# Adafruit_PyPortal.net
KiCad netlist of a schematic drawn in EAGLE
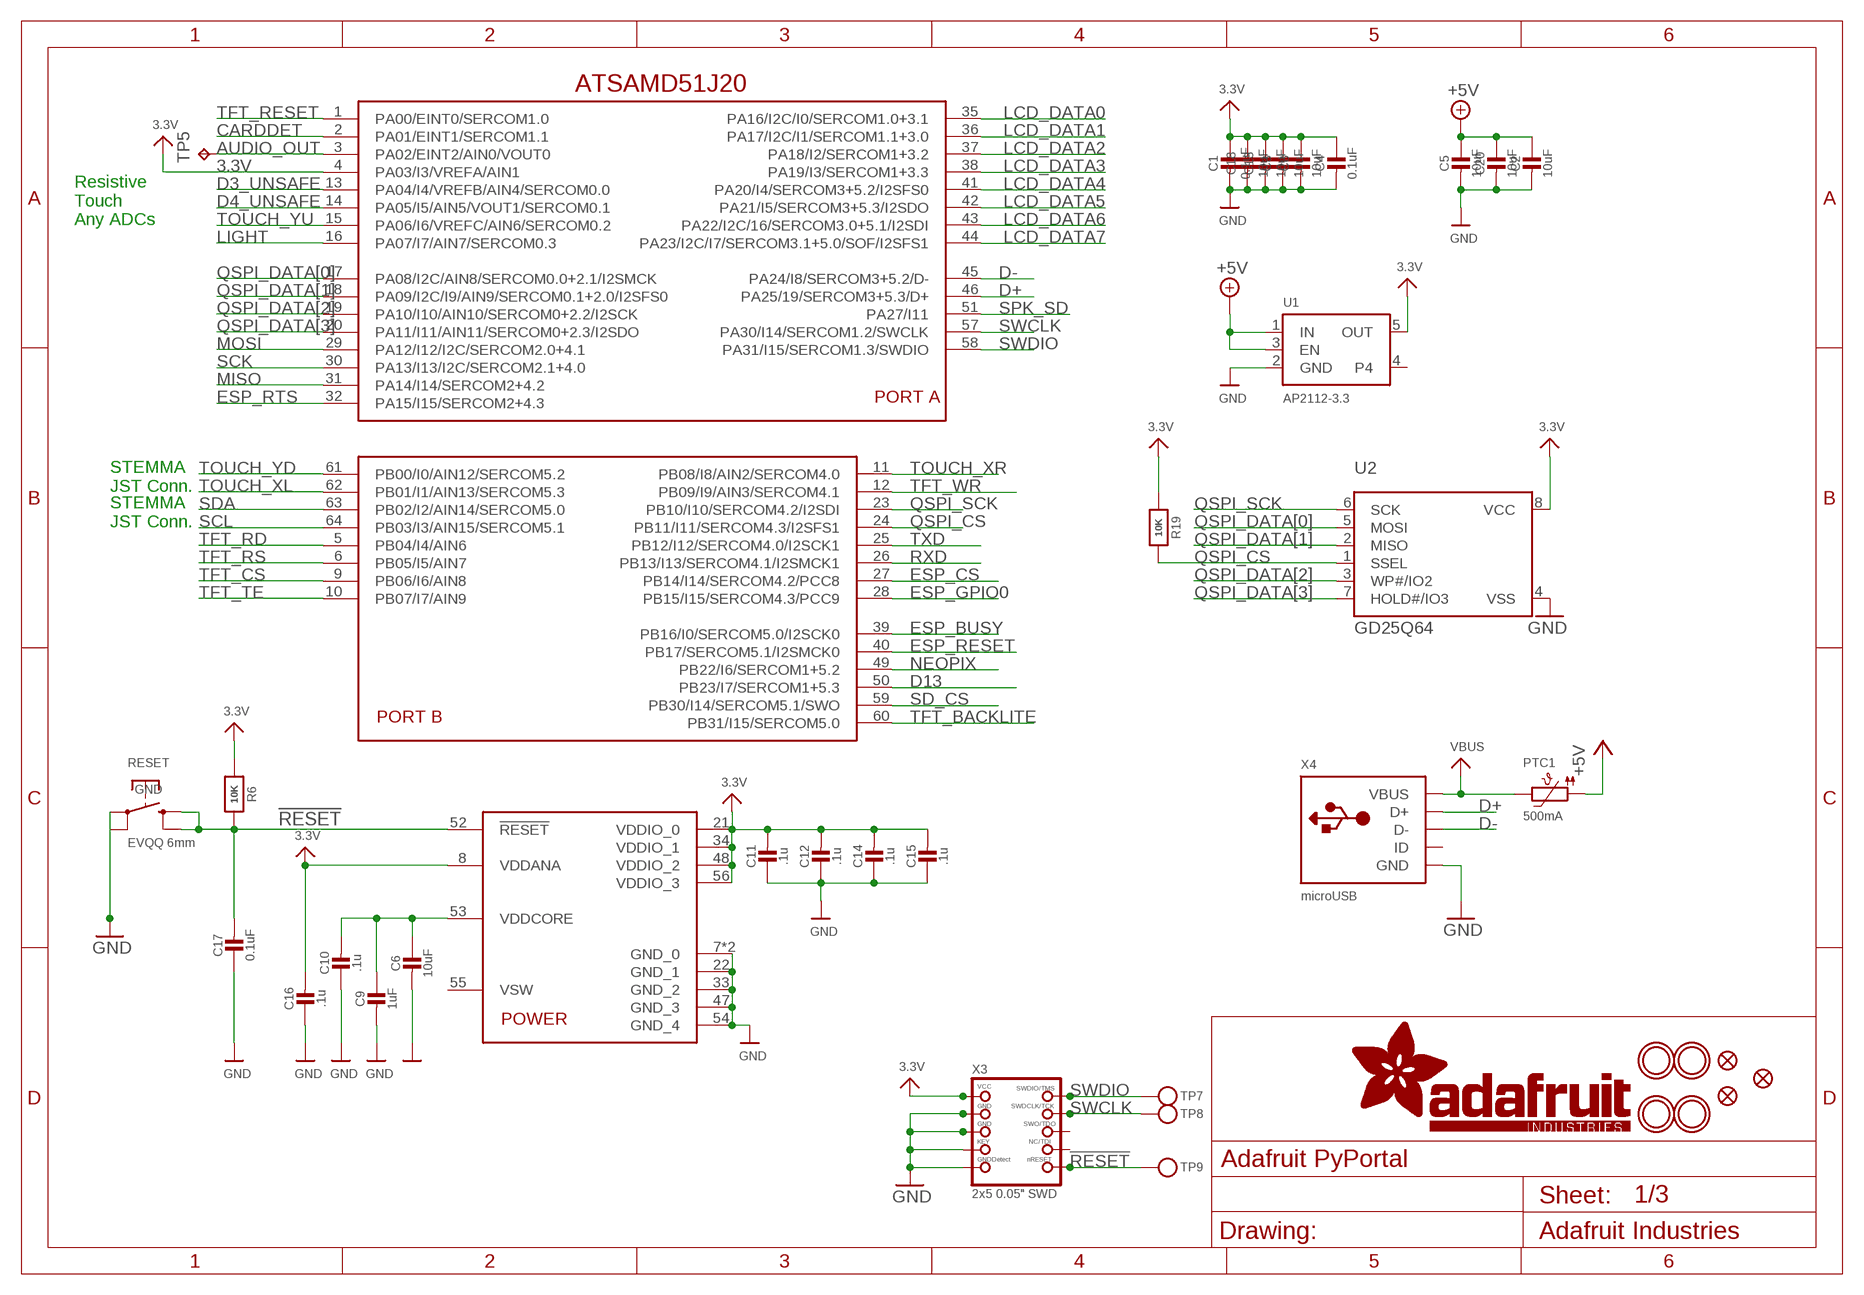
[diagram p0: schematic, sheet 1]
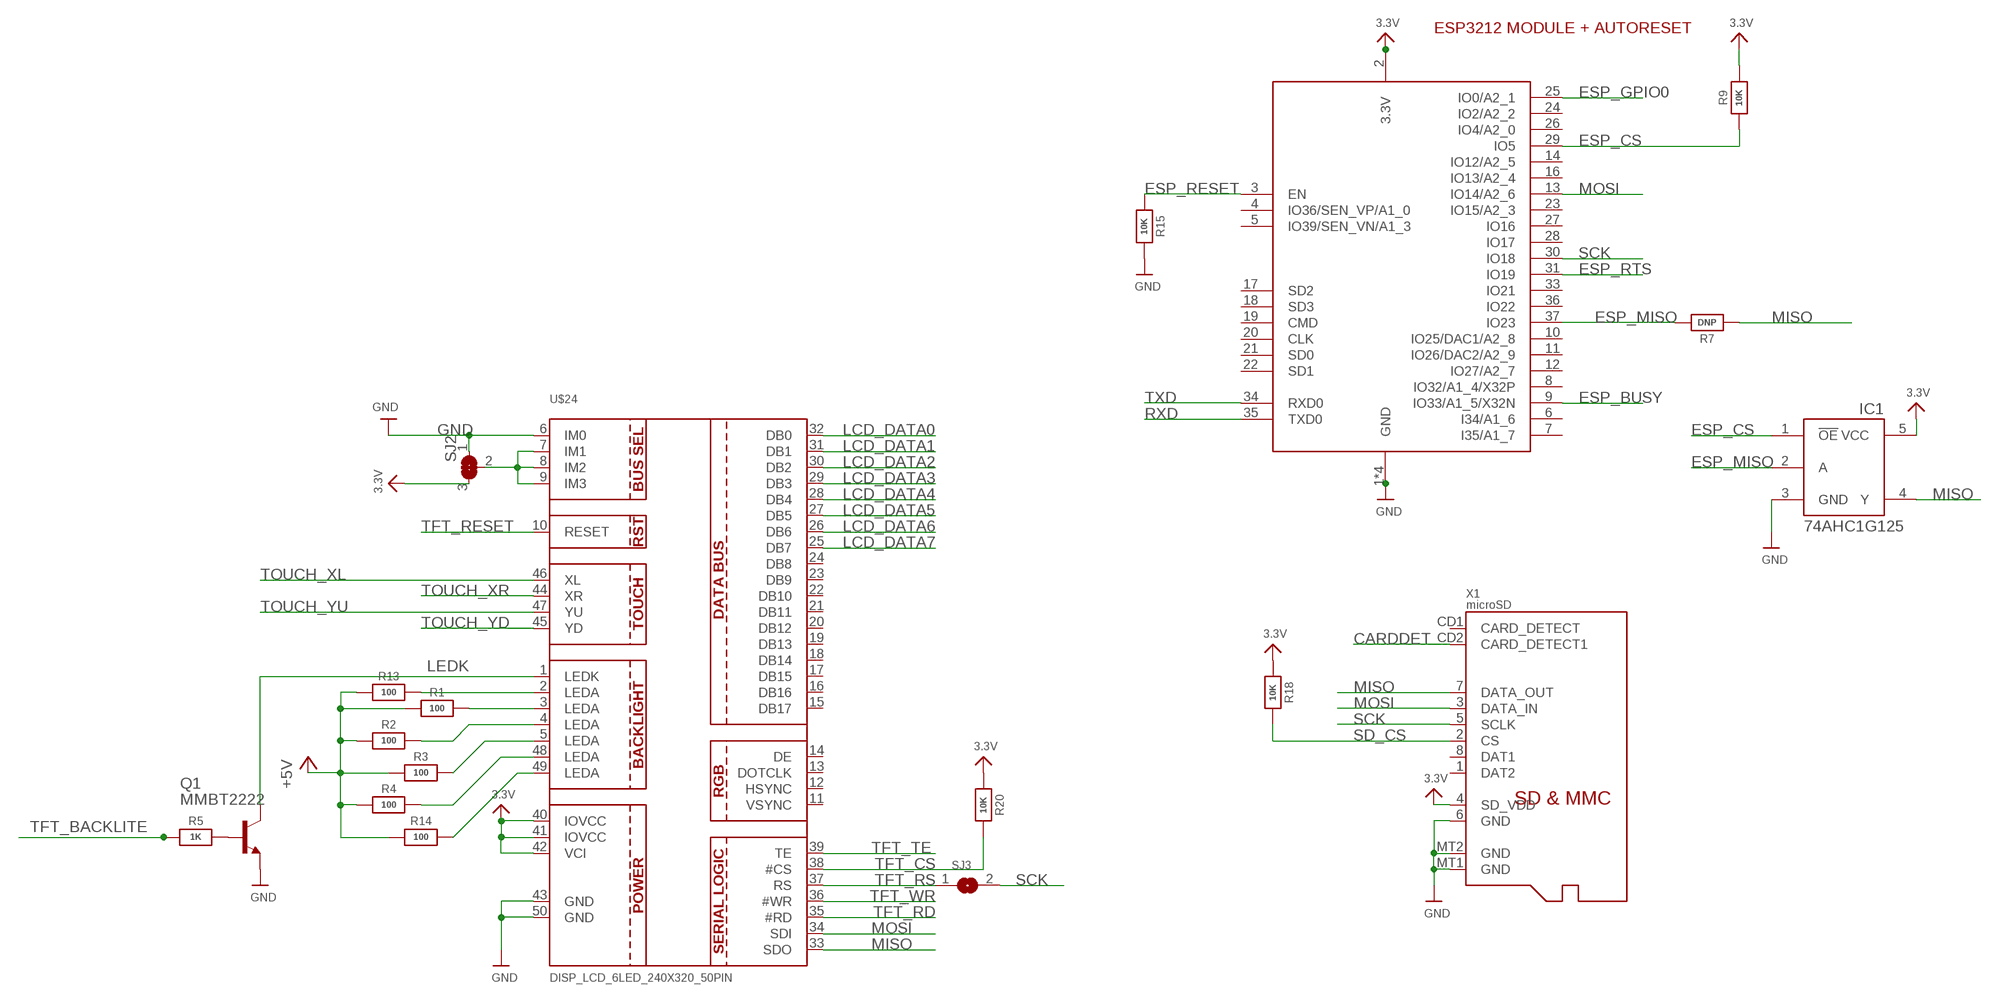
[diagram p1: schematic, sheet 2]
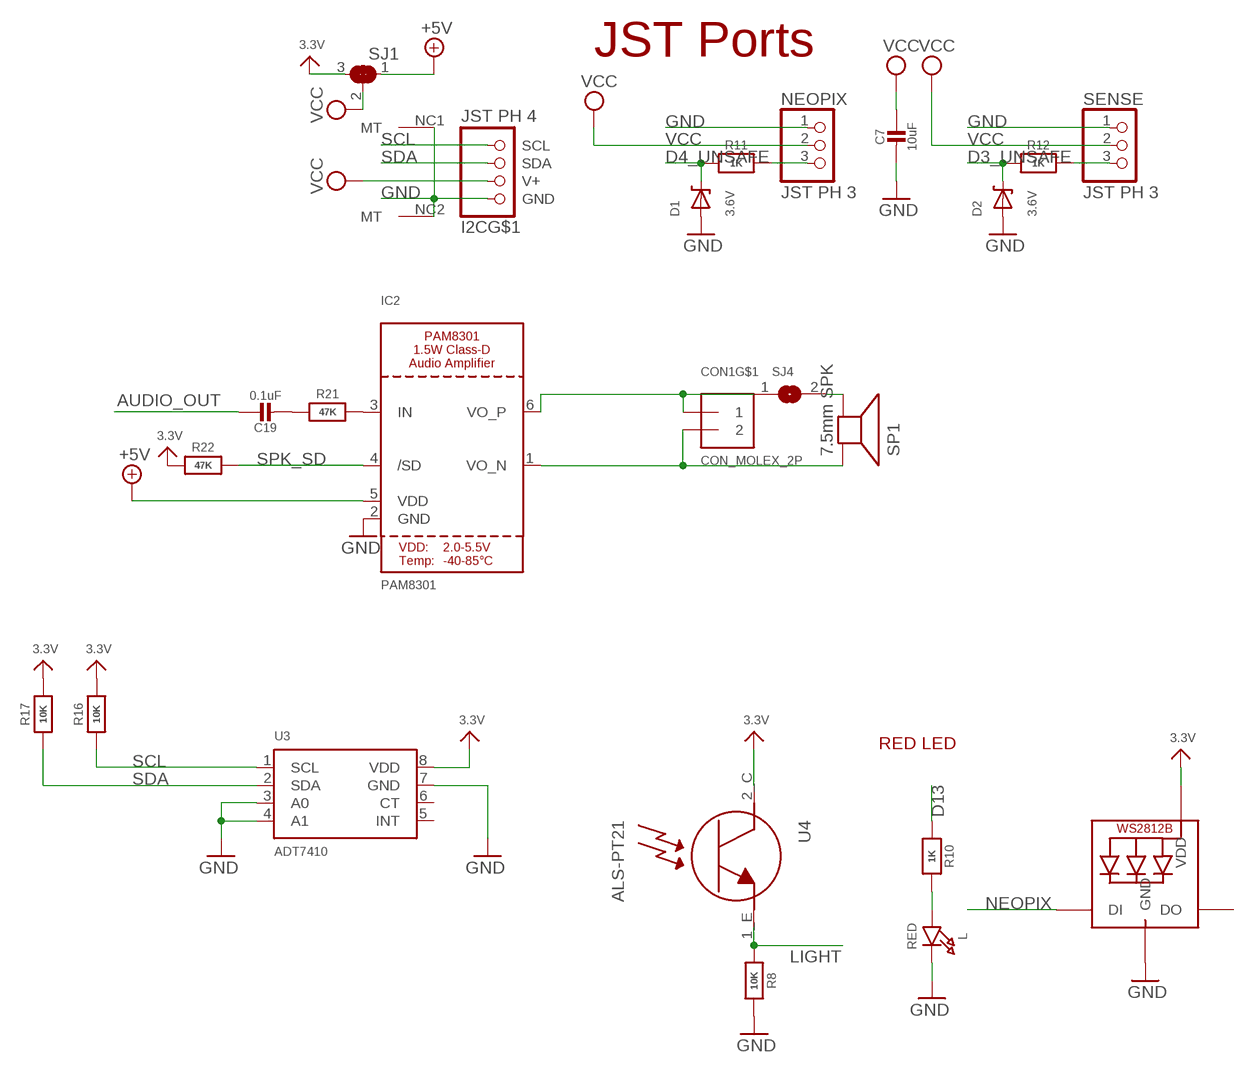
[diagram p2: schematic, sheet 3]

(export (version "E")
  (design (tool "Eeschema 10.0.6"))
  (components
    (comp (ref "IC1")
      (value "74AHC1G125")
      (footprint "eagle-import:SOT23-5L")
      (libsource (lib "eagle-import") (part "74AHC1G125"))
    )
    (comp (ref "Q1")
      (value "MMBT2222")
      (footprint "eagle-import:SOT23-BEC")
      (libsource (lib "eagle-import") (part "-NPN-SOT23-BECMMBT2222ALT1"))
    )
    (comp (ref "R1")
      (value "100")
      (footprint "eagle-import:0603-NO")
      (libsource (lib "eagle-import") (part "RESISTOR_0603_NOOUT"))
    )
    (comp (ref "R2")
      (value "100")
      (footprint "eagle-import:0603-NO")
      (libsource (lib "eagle-import") (part "RESISTOR_0603_NOOUT"))
    )
    (comp (ref "R3")
      (value "100")
      (footprint "eagle-import:0603-NO")
      (libsource (lib "eagle-import") (part "RESISTOR_0603_NOOUT"))
    )
    (comp (ref "R4")
      (value "100")
      (footprint "eagle-import:0603-NO")
      (libsource (lib "eagle-import") (part "RESISTOR_0603_NOOUT"))
    )
    (comp (ref "R5")
      (value "1K")
      (footprint "eagle-import:0603-NO")
      (libsource (lib "eagle-import") (part "RESISTOR_0603_NOOUT"))
    )
    (comp (ref "R7")
      (value "DNP")
      (footprint "eagle-import:0603-NO")
      (libsource (lib "eagle-import") (part "RESISTOR_0603_NOOUT"))
    )
    (comp (ref "R9")
      (value "10K")
      (footprint "eagle-import:0603-NO")
      (libsource (lib "eagle-import") (part "RESISTOR_0603_NOOUT"))
    )
    (comp (ref "R13")
      (value "100")
      (footprint "eagle-import:0603-NO")
      (libsource (lib "eagle-import") (part "RESISTOR_0603_NOOUT"))
    )
    (comp (ref "R14")
      (value "100")
      (footprint "eagle-import:0603-NO")
      (libsource (lib "eagle-import") (part "RESISTOR_0603_NOOUT"))
    )
    (comp (ref "R15")
      (value "10K")
      (footprint "eagle-import:0603-NO")
      (libsource (lib "eagle-import") (part "RESISTOR_0603_NOOUT"))
    )
    (comp (ref "R18")
      (value "10K")
      (footprint "eagle-import:0603-NO")
      (libsource (lib "eagle-import") (part "RESISTOR_0603_NOOUT"))
    )
    (comp (ref "R20")
      (value "10K")
      (footprint "eagle-import:0603-NO")
      (libsource (lib "eagle-import") (part "RESISTOR_0603_NOOUT"))
    )
    (comp (ref "SJ2")
      (value "SOLDERJUMPER_2WAY")
      (footprint "eagle-import:SOLDERJUMPER_2WAY_OPEN_NOPASTE")
      (libsource (lib "eagle-import") (part "SOLDERJUMPER_2WAY"))
    )
    (comp (ref "SJ3")
      (value "SOLDERJUMPER")
      (footprint "eagle-import:SOLDERJUMPER_ARROW_NOPASTE")
      (libsource (lib "eagle-import") (part "SOLDERJUMPER"))
    )
    (comp (ref "U$24")
      (value "DISP_LCD_6LED_240X320_50PIN")
      (footprint "eagle-import:TFT_3.2IN_240X320_50PIN")
      (libsource (lib "eagle-import") (part "DISP_LCD_6LED_240X320_50PIN"))
    )
    (comp (ref "X1")
      (value "microSD")
      (footprint "eagle-import:MICROSD")
      (libsource (lib "eagle-import") (part "MICROSD"))
    )
    (comp (ref "X6")
      (value "ESP32_WROOM32")
      (footprint "eagle-import:WROOM32")
      (libsource (lib "eagle-import") (part "ESP32_WROOM32"))
    )
    (comp (ref "C1")
      (value "0.1uF")
      (footprint "eagle-import:0603-NO")
      (libsource (lib "eagle-import") (part "CAP_CERAMIC0603_NO"))
    )
    (comp (ref "C2")
      (value "10uF")
      (footprint "eagle-import:0805-NO")
      (libsource (lib "eagle-import") (part "CAP_CERAMIC0805-NOOUTLINE"))
    )
    (comp (ref "C3")
      (value "10uF")
      (footprint "eagle-import:0805-NO")
      (libsource (lib "eagle-import") (part "CAP_CERAMIC0805-NOOUTLINE"))
    )
    (comp (ref "C4")
      (value "0.1uF")
      (footprint "eagle-import:0805-NO")
      (libsource (lib "eagle-import") (part "CAP_CERAMIC0805-NOOUTLINE"))
    )
    (comp (ref "C5")
      (value "10uF")
      (footprint "eagle-import:0805-NO")
      (libsource (lib "eagle-import") (part "CAP_CERAMIC0805-NOOUTLINE"))
    )
    (comp (ref "C6")
      (value "10uF")
      (footprint "eagle-import:0805-NO")
      (libsource (lib "eagle-import") (part "CAP_CERAMIC0805-NOOUTLINE"))
    )
    (comp (ref "C8")
      (value "10uF")
      (footprint "eagle-import:0805-NO")
      (libsource (lib "eagle-import") (part "CAP_CERAMIC0805-NOOUTLINE"))
    )
    (comp (ref "C9")
      (value "1uF")
      (footprint "eagle-import:0603-NO")
      (libsource (lib "eagle-import") (part "CAP_CERAMIC0603_NO"))
    )
    (comp (ref "C10")
      (value ".1u")
      (footprint "eagle-import:0603-NO")
      (libsource (lib "eagle-import") (part "CAP_CERAMIC0603_NO"))
    )
    (comp (ref "C11")
      (value ".1u")
      (footprint "eagle-import:0603-NO")
      (libsource (lib "eagle-import") (part "CAP_CERAMIC0603_NO"))
    )
    (comp (ref "C12")
      (value ".1u")
      (footprint "eagle-import:0603-NO")
      (libsource (lib "eagle-import") (part "CAP_CERAMIC0603_NO"))
    )
    (comp (ref "C13")
      (value "10uF")
      (footprint "eagle-import:0805-NO")
      (libsource (lib "eagle-import") (part "CAP_CERAMIC0805-NOOUTLINE"))
    )
    (comp (ref "C14")
      (value ".1u")
      (footprint "eagle-import:0603-NO")
      (libsource (lib "eagle-import") (part "CAP_CERAMIC0603_NO"))
    )
    (comp (ref "C15")
      (value ".1u")
      (footprint "eagle-import:0603-NO")
      (libsource (lib "eagle-import") (part "CAP_CERAMIC0603_NO"))
    )
    (comp (ref "C16")
      (value ".1u")
      (footprint "eagle-import:0603-NO")
      (libsource (lib "eagle-import") (part "CAP_CERAMIC0603_NO"))
    )
    (comp (ref "C17")
      (value "0.1uF")
      (footprint "eagle-import:0603-NO")
      (libsource (lib "eagle-import") (part "CAP_CERAMIC0603_NO"))
    )
    (comp (ref "C18")
      (value "10uF")
      (footprint "eagle-import:0805-NO")
      (libsource (lib "eagle-import") (part "CAP_CERAMIC0805-NOOUTLINE"))
    )
    (comp (ref "C20")
      (value "10uF")
      (footprint "eagle-import:0805-NO")
      (libsource (lib "eagle-import") (part "CAP_CERAMIC0805-NOOUTLINE"))
    )
    (comp (ref "PTC1")
      (value "500mA")
      (footprint "eagle-import:1206")
      (libsource (lib "eagle-import") (part "PTC1206"))
    )
    (comp (ref "R6")
      (value "10K")
      (footprint "eagle-import:0603-NO")
      (libsource (lib "eagle-import") (part "RESISTOR_0603_NOOUT"))
    )
    (comp (ref "R19")
      (value "10K")
      (footprint "eagle-import:0603-NO")
      (libsource (lib "eagle-import") (part "RESISTOR_0603_NOOUT"))
    )
    (comp (ref "RESET")
      (value "EVQQ 6mm")
      (footprint "eagle-import:EVQ-Q2_SMALLER")
      (libsource (lib "eagle-import") (part "SWITCH_TACT_SMT_EVQQ2_SMALL"))
    )
    (comp (ref "TP5")
      (value "TPTP15R")
      (footprint "eagle-import:TP15R")
      (libsource (lib "eagle-import") (part "TPTP15R"))
    )
    (comp (ref "TP7")
      (value "TESTPOINTROUND1.5MM")
      (footprint "eagle-import:TESTPOINT_ROUND_1.5MM")
      (libsource (lib "eagle-import") (part "TESTPOINTROUND1.5MM"))
    )
    (comp (ref "TP8")
      (value "TESTPOINTROUND1.5MM")
      (footprint "eagle-import:TESTPOINT_ROUND_1.5MM")
      (libsource (lib "eagle-import") (part "TESTPOINTROUND1.5MM"))
    )
    (comp (ref "TP9")
      (value "TESTPOINTROUND1.5MM")
      (footprint "eagle-import:TESTPOINT_ROUND_1.5MM")
      (libsource (lib "eagle-import") (part "TESTPOINTROUND1.5MM"))
    )
    (comp (ref "U$2")
      (value "ATSAMD51J20")
      (footprint "eagle-import:PQFN64-1")
      (libsource (lib "eagle-import") (part "ATSAMD51J"))
    )
    (comp (ref "U$7")
      (value "MOUNTINGHOLE3.0THIN")
      (footprint "eagle-import:MOUNTINGHOLE_3.0_PLATEDTHIN")
      (libsource (lib "eagle-import") (part "MOUNTINGHOLE3.0THIN"))
    )
    (comp (ref "U$9")
      (value "FIDUCIAL_1MM")
      (footprint "eagle-import:FIDUCIAL_1MM")
      (libsource (lib "eagle-import") (part "FIDUCIAL_1MM"))
    )
    (comp (ref "U$11")
      (value "FIDUCIAL_1MM")
      (footprint "eagle-import:FIDUCIAL_1MM")
      (libsource (lib "eagle-import") (part "FIDUCIAL_1MM"))
    )
    (comp (ref "U$15")
      (value "MOUNTINGHOLE3.0THIN")
      (footprint "eagle-import:MOUNTINGHOLE_3.0_PLATEDTHIN")
      (libsource (lib "eagle-import") (part "MOUNTINGHOLE3.0THIN"))
    )
    (comp (ref "U$16")
      (value "MOUNTINGHOLE3.0THIN")
      (footprint "eagle-import:MOUNTINGHOLE_3.0_PLATEDTHIN")
      (libsource (lib "eagle-import") (part "MOUNTINGHOLE3.0THIN"))
    )
    (comp (ref "U$17")
      (value "MOUNTINGHOLE3.0THIN")
      (footprint "eagle-import:MOUNTINGHOLE_3.0_PLATEDTHIN")
      (libsource (lib "eagle-import") (part "MOUNTINGHOLE3.0THIN"))
    )
    (comp (ref "U$23")
      (value "FIDUCIAL_1MM")
      (footprint "eagle-import:FIDUCIAL_1MM")
      (libsource (lib "eagle-import") (part "FIDUCIAL_1MM"))
    )
    (comp (ref "U1")
      (value "AP2112-3.3")
      (footprint "eagle-import:SOT23-5")
      (libsource (lib "eagle-import") (part "VREG_SOT23-5"))
    )
    (comp (ref "U2")
      (value "GD25Q64")
      (footprint "eagle-import:SOIC8_208MIL")
      (libsource (lib "eagle-import") (part "SPIFLASH_8PIN208MIL"))
    )
    (comp (ref "X3")
      (value "2x5 0.05\" SWD")
      (footprint "eagle-import:2X05_1.27MM_BOX_POSTS")
      (libsource (lib "eagle-import") (part "JTAG-CORTEXBOXPOSTS"))
    )
    (comp (ref "X4")
      (value "microUSB")
      (footprint "eagle-import:4UCONN_20329_V2")
      (libsource (lib "eagle-import") (part "USB_MICRO_20329_V2"))
    )
    (comp (ref "C7")
      (value "10uF")
      (footprint "eagle-import:0805-NO")
      (libsource (lib "eagle-import") (part "CAP_CERAMIC0805-NOOUTLINE"))
    )
    (comp (ref "C19")
      (value "0.1uF")
      (footprint "eagle-import:0603-NO")
      (libsource (lib "eagle-import") (part "CAP_CERAMIC0603_NO"))
    )
    (comp (ref "CON1")
      (value "CON_MOLEX_2P")
      (footprint "eagle-import:53398-0271")
      (libsource (lib "eagle-import") (part "CON_MOLEX_2P"))
    )
    (comp (ref "D1")
      (value "3.6V")
      (footprint "eagle-import:SOD-323")
      (libsource (lib "eagle-import") (part "DIODE-ZENERSOD323"))
    )
    (comp (ref "D2")
      (value "3.6V")
      (footprint "eagle-import:SOD-323")
      (libsource (lib "eagle-import") (part "DIODE-ZENERSOD323"))
    )
    (comp (ref "I2C")
      (value "JST PH 4")
      (footprint "eagle-import:JSTPH4")
      (libsource (lib "eagle-import") (part "STEMMA_I2C_RASMT"))
    )
    (comp (ref "IC2")
      (value "PAM8301")
      (footprint "eagle-import:SOT23-6")
      (libsource (lib "eagle-import") (part "PAM8301"))
    )
    (comp (ref "L")
      (value "RED")
      (footprint "eagle-import:CHIPLED_0805_NOOUTLINE")
      (libsource (lib "eagle-import") (part "LED0805_NOOUTLINE"))
    )
    (comp (ref "LED1")
      (value "WS2812B3535")
      (footprint "eagle-import:LED3535")
      (libsource (lib "eagle-import") (part "WS2812B3535"))
    )
    (comp (ref "NEOPIX")
      (value "JST PH 3")
      (footprint "eagle-import:JSTPH3")
      (libsource (lib "eagle-import") (part "CON_JST_PH_3PIN"))
    )
    (comp (ref "R8")
      (value "10K")
      (footprint "eagle-import:0603-NO")
      (libsource (lib "eagle-import") (part "RESISTOR_0603_NOOUT"))
    )
    (comp (ref "R10")
      (value "1K")
      (footprint "eagle-import:0603-NO")
      (libsource (lib "eagle-import") (part "RESISTOR_0603_NOOUT"))
    )
    (comp (ref "R11")
      (value "1K")
      (footprint "eagle-import:0603-NO")
      (libsource (lib "eagle-import") (part "RESISTOR_0603_NOOUT"))
    )
    (comp (ref "R12")
      (value "1K")
      (footprint "eagle-import:0603-NO")
      (libsource (lib "eagle-import") (part "RESISTOR_0603_NOOUT"))
    )
    (comp (ref "R16")
      (value "10K")
      (footprint "eagle-import:0603-NO")
      (libsource (lib "eagle-import") (part "RESISTOR_0603_NOOUT"))
    )
    (comp (ref "R17")
      (value "10K")
      (footprint "eagle-import:0603-NO")
      (libsource (lib "eagle-import") (part "RESISTOR_0603_NOOUT"))
    )
    (comp (ref "R21")
      (value "47K")
      (footprint "eagle-import:0603-NO")
      (libsource (lib "eagle-import") (part "RESISTOR_0603_NOOUT"))
    )
    (comp (ref "R22")
      (value "47K")
      (footprint "eagle-import:0603-NO")
      (libsource (lib "eagle-import") (part "RESISTOR_0603_NOOUT"))
    )
    (comp (ref "SENSE")
      (value "JST PH 3")
      (footprint "eagle-import:JSTPH3")
      (libsource (lib "eagle-import") (part "CON_JST_PH_3PIN"))
    )
    (comp (ref "SJ1")
      (value "SOLDERJUMPER_2WAY")
      (footprint "eagle-import:SOLDERJUMPER_2WAY_OPEN_NOPASTE")
      (libsource (lib "eagle-import") (part "SOLDERJUMPER_2WAY"))
    )
    (comp (ref "SJ4")
      (value "SOLDERJUMPERCLOSED")
      (footprint "eagle-import:SOLDERJUMPER_CLOSEDWIRE")
      (libsource (lib "eagle-import") (part "SOLDERJUMPERCLOSED"))
    )
    (comp (ref "SP1")
      (value "7.5mm SPK")
      (footprint "eagle-import:BUZZER_SMT_7.5MM")
      (libsource (lib "eagle-import") (part "SPEAKER_7.5MM"))
    )
    (comp (ref "U3")
      (value "ADT7410")
      (footprint "eagle-import:SOIC8_150MIL")
      (libsource (lib "eagle-import") (part "TEMP_ADT7410"))
    )
    (comp (ref "U4")
      (value "ALS-PT21")
      (footprint "eagle-import:ALS-PT26-21C")
      (libsource (lib "eagle-import") (part "PHOTOTRANSISTOR_PT26-21C"))
    )
  )
  (nets
    (net (code "1") (name "+5V") (class "Default")
      (node (ref "C2") (pin "1") (pinfunction "1_1") (pintype "passive"))
      (node (ref "C20") (pin "1") (pinfunction "1_1") (pintype "passive"))
      (node (ref "C5") (pin "1") (pinfunction "1_1") (pintype "passive"))
      (node (ref "IC2") (pin "5") (pinfunction "VDD_5") (pintype "power_in"))
      (node (ref "PTC1") (pin "1") (pinfunction "1_1") (pintype "passive"))
      (node (ref "R1") (pin "1") (pinfunction "1_1") (pintype "passive"))
      (node (ref "R13") (pin "1") (pinfunction "1_1") (pintype "passive"))
      (node (ref "R14") (pin "1") (pinfunction "1_1") (pintype "passive"))
      (node (ref "R2") (pin "1") (pinfunction "1_1") (pintype "passive"))
      (node (ref "R3") (pin "1") (pinfunction "1_1") (pintype "passive"))
      (node (ref "R4") (pin "1") (pinfunction "1_1") (pintype "passive"))
      (node (ref "SJ1") (pin "1") (pinfunction "1_1") (pintype "passive"))
      (node (ref "U1") (pin "1") (pinfunction "IN_1") (pintype "power_in"))
      (node (ref "U1") (pin "3") (pinfunction "EN_3") (pintype "input"))
    )
    (net (code "2") (name "3.3V") (class "Default")
      (node (ref "C1") (pin "1") (pinfunction "1_1") (pintype "passive"))
      (node (ref "C11") (pin "2") (pinfunction "2_2") (pintype "passive"))
      (node (ref "C12") (pin "2") (pinfunction "2_2") (pintype "passive"))
      (node (ref "C13") (pin "1") (pinfunction "1_1") (pintype "passive"))
      (node (ref "C14") (pin "2") (pinfunction "2_2") (pintype "passive"))
      (node (ref "C15") (pin "2") (pinfunction "2_2") (pintype "passive"))
      (node (ref "C16") (pin "2") (pinfunction "2_2") (pintype "passive"))
      (node (ref "C18") (pin "1") (pinfunction "1_1") (pintype "passive"))
      (node (ref "C3") (pin "1") (pinfunction "1_1") (pintype "passive"))
      (node (ref "C4") (pin "1") (pinfunction "1_1") (pintype "passive"))
      (node (ref "C8") (pin "1") (pinfunction "1_1") (pintype "passive"))
      (node (ref "IC1") (pin "5") (pinfunction "VCC_5") (pintype "power_in"))
      (node (ref "LED1") (pin "2") (pinfunction "VDD_2") (pintype "power_in"))
      (node (ref "R16") (pin "1") (pinfunction "1_1") (pintype "passive"))
      (node (ref "R17") (pin "1") (pinfunction "1_1") (pintype "passive"))
      (node (ref "R18") (pin "1") (pinfunction "1_1") (pintype "passive"))
      (node (ref "R19") (pin "1") (pinfunction "1_1") (pintype "passive"))
      (node (ref "R20") (pin "1") (pinfunction "1_1") (pintype "passive"))
      (node (ref "R22") (pin "1") (pinfunction "1_1") (pintype "passive"))
      (node (ref "R6") (pin "1") (pinfunction "1_1") (pintype "passive"))
      (node (ref "R9") (pin "2") (pinfunction "2_2") (pintype "passive"))
      (node (ref "SJ1") (pin "3") (pinfunction "3_3") (pintype "passive"))
      (node (ref "SJ2") (pin "3") (pinfunction "3_3") (pintype "passive"))
      (node (ref "U$2") (pin "21") (pinfunction "VDDIO_0_21") (pintype "bidirectional"))
      (node (ref "U$2") (pin "34") (pinfunction "VDDIO_1_34") (pintype "bidirectional"))
      (node (ref "U$2") (pin "4") (pinfunction "PA03/I3/VREFA/AIN1_4") (pintype "bidirectional"))
      (node (ref "U$2") (pin "48") (pinfunction "VDDIO_2_48") (pintype "bidirectional"))
      (node (ref "U$2") (pin "56") (pinfunction "VDDIO_3_56") (pintype "bidirectional"))
      (node (ref "U$2") (pin "8") (pinfunction "VDDANA_8") (pintype "bidirectional"))
      (node (ref "U$24") (pin "40") (pinfunction "IOVCC_40") (pintype "bidirectional"))
      (node (ref "U$24") (pin "41") (pinfunction "IOVCC_41") (pintype "bidirectional"))
      (node (ref "U$24") (pin "42") (pinfunction "VCI_42") (pintype "bidirectional"))
      (node (ref "U1") (pin "5") (pinfunction "OUT_5") (pintype "power_in"))
      (node (ref "U2") (pin "8") (pinfunction "VCC_8") (pintype "bidirectional"))
      (node (ref "U3") (pin "8") (pinfunction "VDD_8") (pintype "power_in"))
      (node (ref "U4") (pin "2_C") (pinfunction "C_2_C") (pintype "bidirectional"))
      (node (ref "X1") (pin "4") (pinfunction "SD_VDD_4") (pintype "power_in"))
      (node (ref "X3") (pin "1") (pinfunction "VCC_1") (pintype "power_in"))
      (node (ref "X6") (pin "2") (pinfunction "3.3V_2") (pintype "passive"))
    )
    (net (code "3") (name "AUDIO_OUT") (class "Default")
      (node (ref "C19") (pin "1") (pinfunction "1_1") (pintype "passive"))
      (node (ref "TP5") (pin "TP") (pinfunction "TP_TP") (pintype "input"))
      (node (ref "U$2") (pin "3") (pinfunction "PA02/EINT2/AIN0/VOUT0_3") (pintype "bidirectional"))
    )
    (net (code "4") (name "CARDDET") (class "Default")
      (node (ref "U$2") (pin "2") (pinfunction "PA01/EINT1/SERCOM1.1_2") (pintype "bidirectional"))
      (node (ref "X1") (pin "CD2") (pinfunction "CARD_DETECT1_CD2") (pintype "passive"))
    )
    (net (code "5") (name "D+") (class "Default")
      (node (ref "U$2") (pin "46") (pinfunction "PA25/19/SERCOM3+5.3/D+_46") (pintype "bidirectional"))
      (node (ref "X4") (pin "D+") (pinfunction "D+_D+") (pintype "bidirectional"))
    )
    (net (code "6") (name "D-") (class "Default")
      (node (ref "U$2") (pin "45") (pinfunction "PA24/I8/SERCOM3+5.2/D-_45") (pintype "bidirectional"))
      (node (ref "X4") (pin "D-") (pinfunction "D-_D-") (pintype "bidirectional"))
    )
    (net (code "7") (name "D3_UNSAFE") (class "Default")
      (node (ref "D2") (pin "C") (pinfunction "C_C") (pintype "passive"))
      (node (ref "R12") (pin "2") (pinfunction "2_2") (pintype "passive"))
      (node (ref "U$2") (pin "13") (pinfunction "PA04/I4/VREFB/AIN4/SERCOM0.0_13") (pintype "bidirectional"))
    )
    (net (code "8") (name "D4_UNSAFE") (class "Default")
      (node (ref "D1") (pin "C") (pinfunction "C_C") (pintype "passive"))
      (node (ref "R11") (pin "2") (pinfunction "2_2") (pintype "passive"))
      (node (ref "U$2") (pin "14") (pinfunction "PA05/I5/AIN5/VOUT1/SERCOM0.1_14") (pintype "bidirectional"))
    )
    (net (code "9") (name "D13") (class "Default")
      (node (ref "R10") (pin "1") (pinfunction "1_1") (pintype "passive"))
      (node (ref "U$2") (pin "50") (pinfunction "PB23/I7/SERCOM1+5.3_50") (pintype "bidirectional"))
    )
    (net (code "10") (name "ESP_BUSY") (class "Default")
      (node (ref "U$2") (pin "39") (pinfunction "PB16/I0/SERCOM5.0/I2SCK0_39") (pintype "bidirectional"))
      (node (ref "X6") (pin "9") (pinfunction "IO33/A1_5/X32N_9") (pintype "bidirectional"))
    )
    (net (code "11") (name "ESP_CS") (class "Default")
      (node (ref "IC1") (pin "1") (pinfunction "~{OE}_1") (pintype "input"))
      (node (ref "R9") (pin "1") (pinfunction "1_1") (pintype "passive"))
      (node (ref "U$2") (pin "27") (pinfunction "PB14/I14/SERCOM4.2/PCC8_27") (pintype "bidirectional"))
      (node (ref "X6") (pin "29") (pinfunction "IO5_29") (pintype "bidirectional"))
    )
    (net (code "12") (name "ESP_GPIO0") (class "Default")
      (node (ref "U$2") (pin "28") (pinfunction "PB15/I15/SERCOM4.3/PCC9_28") (pintype "bidirectional"))
      (node (ref "X6") (pin "25") (pinfunction "IO0/A2_1_25") (pintype "bidirectional"))
    )
    (net (code "13") (name "ESP_MISO") (class "Default")
      (node (ref "IC1") (pin "2") (pinfunction "A_2") (pintype "input"))
      (node (ref "R7") (pin "2") (pinfunction "2_2") (pintype "passive"))
      (node (ref "X6") (pin "37") (pinfunction "IO23_37") (pintype "bidirectional"))
    )
    (net (code "14") (name "ESP_RESET") (class "Default")
      (node (ref "R15") (pin "1") (pinfunction "1_1") (pintype "passive"))
      (node (ref "U$2") (pin "40") (pinfunction "PB17/SERCOM5.1/I2SMCK0_40") (pintype "bidirectional"))
      (node (ref "X6") (pin "3") (pinfunction "EN_3") (pintype "input"))
    )
    (net (code "15") (name "ESP_RTS") (class "Default")
      (node (ref "U$2") (pin "32") (pinfunction "PA15/I15/SERCOM2+4.3_32") (pintype "bidirectional"))
      (node (ref "X6") (pin "31") (pinfunction "IO19_31") (pintype "bidirectional"))
    )
    (net (code "16") (name "GND") (class "Default")
      (node (ref "C1") (pin "2") (pinfunction "2_2") (pintype "passive"))
      (node (ref "C10") (pin "1") (pinfunction "1_1") (pintype "passive"))
      (node (ref "C11") (pin "1") (pinfunction "1_1") (pintype "passive"))
      (node (ref "C12") (pin "1") (pinfunction "1_1") (pintype "passive"))
      (node (ref "C13") (pin "2") (pinfunction "2_2") (pintype "passive"))
      (node (ref "C14") (pin "1") (pinfunction "1_1") (pintype "passive"))
      (node (ref "C15") (pin "1") (pinfunction "1_1") (pintype "passive"))
      (node (ref "C16") (pin "1") (pinfunction "1_1") (pintype "passive"))
      (node (ref "C17") (pin "1") (pinfunction "1_1") (pintype "passive"))
      (node (ref "C18") (pin "2") (pinfunction "2_2") (pintype "passive"))
      (node (ref "C2") (pin "2") (pinfunction "2_2") (pintype "passive"))
      (node (ref "C20") (pin "2") (pinfunction "2_2") (pintype "passive"))
      (node (ref "C3") (pin "2") (pinfunction "2_2") (pintype "passive"))
      (node (ref "C4") (pin "2") (pinfunction "2_2") (pintype "passive"))
      (node (ref "C5") (pin "2") (pinfunction "2_2") (pintype "passive"))
      (node (ref "C6") (pin "2") (pinfunction "2_2") (pintype "passive"))
      (node (ref "C7") (pin "2") (pinfunction "2_2") (pintype "passive"))
      (node (ref "C8") (pin "2") (pinfunction "2_2") (pintype "passive"))
      (node (ref "C9") (pin "2") (pinfunction "2_2") (pintype "passive"))
      (node (ref "D1") (pin "A") (pinfunction "A_A") (pintype "passive"))
      (node (ref "D2") (pin "A") (pinfunction "A_A") (pintype "passive"))
      (node (ref "I2C") (pin "1") (pinfunction "GND_1") (pintype "passive"))
      (node (ref "I2C") (pin "NC1") (pinfunction "MT_NC1") (pintype "bidirectional"))
      (node (ref "I2C") (pin "NC2") (pinfunction "MT_NC2") (pintype "bidirectional"))
      (node (ref "IC1") (pin "3") (pinfunction "GND_3") (pintype "power_in"))
      (node (ref "IC2") (pin "2") (pinfunction "GND_2") (pintype "power_in"))
      (node (ref "L") (pin "C") (pinfunction "C_C") (pintype "passive"))
      (node (ref "LED1") (pin "4") (pinfunction "GND_4") (pintype "power_in"))
      (node (ref "NEOPIX") (pin "1") (pinfunction "1_1") (pintype "passive"))
      (node (ref "Q1") (pin "E") (pinfunction "E_E") (pintype "passive"))
      (node (ref "R15") (pin "2") (pinfunction "2_2") (pintype "passive"))
      (node (ref "R8") (pin "1") (pinfunction "1_1") (pintype "passive"))
      (node (ref "RESET") (pin "A") (pinfunction "P_A") (pintype "passive"))
      (node (ref "RESET") (pin "A'") (pinfunction "P1_A'") (pintype "passive"))
      (node (ref "SENSE") (pin "1") (pinfunction "1_1") (pintype "passive"))
      (node (ref "SJ2") (pin "1") (pinfunction "1_1") (pintype "passive"))
      (node (ref "U$2") (pin "22") (pinfunction "GND_1_22") (pintype "bidirectional"))
      (node (ref "U$2") (pin "33") (pinfunction "GND_2_33") (pintype "bidirectional"))
      (node (ref "U$2") (pin "47") (pinfunction "GND_3_47") (pintype "bidirectional"))
      (node (ref "U$2") (pin "54") (pinfunction "GND_4_54") (pintype "bidirectional"))
      (node (ref "U$2") (pin "7") (pinfunction "GND_0_7") (pintype "bidirectional"))
      (node (ref "U$2") (pin "EXP") (pinfunction "GND_0_EXP") (pintype "bidirectional"))
      (node (ref "U$24") (pin "43") (pinfunction "GND_43") (pintype "bidirectional"))
      (node (ref "U$24") (pin "50") (pinfunction "GND_50") (pintype "bidirectional"))
      (node (ref "U$24") (pin "6") (pinfunction "IM0_6") (pintype "bidirectional"))
      (node (ref "U1") (pin "2") (pinfunction "GND_2") (pintype "power_in"))
      (node (ref "U2") (pin "4") (pinfunction "VSS_4") (pintype "bidirectional"))
      (node (ref "U3") (pin "3") (pinfunction "A0_3") (pintype "bidirectional"))
      (node (ref "U3") (pin "4") (pinfunction "A1_4") (pintype "bidirectional"))
      (node (ref "U3") (pin "7") (pinfunction "GND_7") (pintype "power_in"))
      (node (ref "X1") (pin "6") (pinfunction "GND_6") (pintype "power_in"))
      (node (ref "X1") (pin "MT1") (pinfunction "GND_MT1") (pintype "power_in"))
      (node (ref "X1") (pin "MT2") (pinfunction "GND_MT2") (pintype "power_in"))
      (node (ref "X3") (pin "3") (pinfunction "GND_3") (pintype "power_in"))
      (node (ref "X3") (pin "5") (pinfunction "GND_5") (pintype "power_in"))
      (node (ref "X3") (pin "7") (pinfunction "KEY_7") (pintype "bidirectional"))
      (node (ref "X3") (pin "9") (pinfunction "GNDDETECT_9") (pintype "bidirectional"))
      (node (ref "X4") (pin "BASE@1") (pinfunction "GND_BASE@1") (pintype "power_in"))
      (node (ref "X4") (pin "BASE@2") (pinfunction "GND_BASE@2") (pintype "power_in"))
      (node (ref "X4") (pin "GND") (pinfunction "GND_GND") (pintype "power_in"))
      (node (ref "X4") (pin "SPRT@1") (pinfunction "GND_SPRT@1") (pintype "power_in"))
      (node (ref "X4") (pin "SPRT@2") (pinfunction "GND_SPRT@2") (pintype "power_in"))
      (node (ref "X4") (pin "SPRT@3") (pinfunction "GND_SPRT@3") (pintype "power_in"))
      (node (ref "X4") (pin "SPRT@4") (pinfunction "GND_SPRT@4") (pintype "power_in"))
      (node (ref "X6") (pin "1") (pinfunction "GND_1") (pintype "passive"))
      (node (ref "X6") (pin "15") (pinfunction "GND_15") (pintype "passive"))
      (node (ref "X6") (pin "38") (pinfunction "GND_38") (pintype "passive"))
      (node (ref "X6") (pin "P$1") (pinfunction "GND_P$1") (pintype "passive"))
    )
    (net (code "17") (name "LCD_DATA0") (class "Default")
      (node (ref "U$2") (pin "35") (pinfunction "PA16/I2C/I0/SERCOM1.0+3.1_35") (pintype "bidirectional"))
      (node (ref "U$24") (pin "32") (pinfunction "DB0_32") (pintype "bidirectional"))
    )
    (net (code "18") (name "LCD_DATA1") (class "Default")
      (node (ref "U$2") (pin "36") (pinfunction "PA17/I2C/I1/SERCOM1.1+3.0_36") (pintype "bidirectional"))
      (node (ref "U$24") (pin "31") (pinfunction "DB1_31") (pintype "bidirectional"))
    )
    (net (code "19") (name "LCD_DATA2") (class "Default")
      (node (ref "U$2") (pin "37") (pinfunction "PA18/I2/SERCOM1+3.2_37") (pintype "bidirectional"))
      (node (ref "U$24") (pin "30") (pinfunction "DB2_30") (pintype "bidirectional"))
    )
    (net (code "20") (name "LCD_DATA3") (class "Default")
      (node (ref "U$2") (pin "38") (pinfunction "PA19/I3/SERCOM1+3.3_38") (pintype "bidirectional"))
      (node (ref "U$24") (pin "29") (pinfunction "DB3_29") (pintype "bidirectional"))
    )
    (net (code "21") (name "LCD_DATA4") (class "Default")
      (node (ref "U$2") (pin "41") (pinfunction "PA20/I4/SERCOM3+5.2/I2SFS0_41") (pintype "bidirectional"))
      (node (ref "U$24") (pin "28") (pinfunction "DB4_28") (pintype "bidirectional"))
    )
    (net (code "22") (name "LCD_DATA5") (class "Default")
      (node (ref "U$2") (pin "42") (pinfunction "PA21/I5/SERCOM3+5.3/I2SDO_42") (pintype "bidirectional"))
      (node (ref "U$24") (pin "27") (pinfunction "DB5_27") (pintype "bidirectional"))
    )
    (net (code "23") (name "LCD_DATA6") (class "Default")
      (node (ref "U$2") (pin "43") (pinfunction "PA22/I2C/16/SERCOM3.0+5.1/I2SDI_43") (pintype "bidirectional"))
      (node (ref "U$24") (pin "26") (pinfunction "DB6_26") (pintype "bidirectional"))
    )
    (net (code "24") (name "LCD_DATA7") (class "Default")
      (node (ref "U$2") (pin "44") (pinfunction "PA23/I2C/I7/SERCOM3.1+5.0/SOF/I2SFS1_44") (pintype "bidirectional"))
      (node (ref "U$24") (pin "25") (pinfunction "DB7_25") (pintype "bidirectional"))
    )
    (net (code "25") (name "LEDK") (class "Default")
      (node (ref "Q1") (pin "C") (pinfunction "C_C") (pintype "passive"))
      (node (ref "U$24") (pin "1") (pinfunction "LEDK_1") (pintype "bidirectional"))
    )
    (net (code "26") (name "LIGHT") (class "Default")
      (node (ref "R8") (pin "2") (pinfunction "2_2") (pintype "passive"))
      (node (ref "U$2") (pin "16") (pinfunction "PA07/I7/AIN7/SERCOM0.3_16") (pintype "bidirectional"))
      (node (ref "U4") (pin "1_E") (pinfunction "E_1_E") (pintype "bidirectional"))
    )
    (net (code "27") (name "MISO") (class "Default")
      (node (ref "IC1") (pin "4") (pinfunction "Y_4") (pintype "output"))
      (node (ref "R7") (pin "1") (pinfunction "1_1") (pintype "passive"))
      (node (ref "U$2") (pin "31") (pinfunction "PA14/I14/SERCOM2+4.2_31") (pintype "bidirectional"))
      (node (ref "U$24") (pin "33") (pinfunction "SDO_33") (pintype "bidirectional"))
      (node (ref "X1") (pin "7") (pinfunction "DATA_OUT_7") (pintype "output"))
    )
    (net (code "28") (name "MOSI") (class "Default")
      (node (ref "U$2") (pin "29") (pinfunction "PA12/I12/I2C/SERCOM2.0+4.1_29") (pintype "bidirectional"))
      (node (ref "U$24") (pin "34") (pinfunction "SDI_34") (pintype "bidirectional"))
      (node (ref "X1") (pin "3") (pinfunction "DATA_IN_3") (pintype "input"))
      (node (ref "X6") (pin "13") (pinfunction "IO14/A2_6_13") (pintype "bidirectional"))
    )
    (net (code "29") (name "NEOPIX") (class "Default")
      (node (ref "LED1") (pin "1") (pinfunction "DI_1") (pintype "input"))
      (node (ref "U$2") (pin "49") (pinfunction "PB22/I6/SERCOM1+5.2_49") (pintype "bidirectional"))
    )
    (net (code "30") (name "Net-(C19-Pad2)") (class "Default")
      (node (ref "C19") (pin "2") (pinfunction "2_2") (pintype "passive"))
      (node (ref "R21") (pin "1") (pinfunction "1_1") (pintype "passive"))
    )
    (net (code "31") (name "Net-(IC2-IN)") (class "Default")
      (node (ref "IC2") (pin "3") (pinfunction "IN_3") (pintype "input"))
      (node (ref "R21") (pin "2") (pinfunction "2_2") (pintype "passive"))
    )
    (net (code "32") (name "Net-(IC2-VO_N)") (class "Default")
      (node (ref "CON1") (pin "2") (pinfunction "2_2") (pintype "passive"))
      (node (ref "IC2") (pin "1") (pinfunction "VO_N_1") (pintype "output"))
      (node (ref "SP1") (pin "+") (pinfunction "+_+") (pintype "passive"))
    )
    (net (code "33") (name "Net-(IC2-VO_P)") (class "Default")
      (node (ref "CON1") (pin "1") (pinfunction "1_1") (pintype "passive"))
      (node (ref "IC2") (pin "6") (pinfunction "VO_P_6") (pintype "output"))
      (node (ref "SJ4") (pin "1") (pinfunction "1_1") (pintype "passive"))
    )
    (net (code "34") (name "Net-(L-PadA)") (class "Default")
      (node (ref "L") (pin "A") (pinfunction "A_A") (pintype "passive"))
      (node (ref "R10") (pin "2") (pinfunction "2_2") (pintype "passive"))
    )
    (net (code "35") (name "Net-(NEOPIX-Pad3)") (class "Default")
      (node (ref "NEOPIX") (pin "3") (pinfunction "3_3") (pintype "passive"))
      (node (ref "R11") (pin "1") (pinfunction "1_1") (pintype "passive"))
    )
    (net (code "36") (name "Net-(Q1-PadB)") (class "Default")
      (node (ref "Q1") (pin "B") (pinfunction "B_B") (pintype "passive"))
      (node (ref "R5") (pin "2") (pinfunction "2_2") (pintype "passive"))
    )
    (net (code "37") (name "Net-(R1-Pad2)") (class "Default")
      (node (ref "R1") (pin "2") (pinfunction "2_2") (pintype "passive"))
      (node (ref "U$24") (pin "3") (pinfunction "LEDA_3") (pintype "bidirectional"))
    )
    (net (code "38") (name "Net-(R2-Pad2)") (class "Default")
      (node (ref "R2") (pin "2") (pinfunction "2_2") (pintype "passive"))
      (node (ref "U$24") (pin "4") (pinfunction "LEDA_4") (pintype "bidirectional"))
    )
    (net (code "39") (name "Net-(R3-Pad2)") (class "Default")
      (node (ref "R3") (pin "2") (pinfunction "2_2") (pintype "passive"))
      (node (ref "U$24") (pin "5") (pinfunction "LEDA_5") (pintype "bidirectional"))
    )
    (net (code "40") (name "Net-(R4-Pad2)") (class "Default")
      (node (ref "R4") (pin "2") (pinfunction "2_2") (pintype "passive"))
      (node (ref "U$24") (pin "48") (pinfunction "LEDA_48") (pintype "bidirectional"))
    )
    (net (code "41") (name "Net-(R12-Pad1)") (class "Default")
      (node (ref "R12") (pin "1") (pinfunction "1_1") (pintype "passive"))
      (node (ref "SENSE") (pin "3") (pinfunction "3_3") (pintype "passive"))
    )
    (net (code "42") (name "Net-(R13-Pad2)") (class "Default")
      (node (ref "R13") (pin "2") (pinfunction "2_2") (pintype "passive"))
      (node (ref "U$24") (pin "2") (pinfunction "LEDA_2") (pintype "bidirectional"))
    )
    (net (code "43") (name "Net-(R14-Pad2)") (class "Default")
      (node (ref "R14") (pin "2") (pinfunction "2_2") (pintype "passive"))
      (node (ref "U$24") (pin "49") (pinfunction "LEDA_49") (pintype "bidirectional"))
    )
    (net (code "44") (name "Net-(SJ4-Pad2)") (class "Default")
      (node (ref "SJ4") (pin "2") (pinfunction "2_2") (pintype "passive"))
      (node (ref "SP1") (pin "-") (pinfunction "-_-") (pintype "passive"))
    )
    (net (code "45") (name "Net-(U$2C-VDDCORE)") (class "Default")
      (node (ref "C10") (pin "2") (pinfunction "2_2") (pintype "passive"))
      (node (ref "C6") (pin "1") (pinfunction "1_1") (pintype "passive"))
      (node (ref "C9") (pin "1") (pinfunction "1_1") (pintype "passive"))
      (node (ref "U$2") (pin "53") (pinfunction "VDDCORE_53") (pintype "bidirectional"))
    )
    (net (code "46") (name "Net-(U$24-IM1)") (class "Default")
      (node (ref "SJ2") (pin "2") (pinfunction "2_2") (pintype "passive"))
      (node (ref "U$24") (pin "7") (pinfunction "IM1_7") (pintype "bidirectional"))
      (node (ref "U$24") (pin "8") (pinfunction "IM2_8") (pintype "bidirectional"))
      (node (ref "U$24") (pin "9") (pinfunction "IM3_9") (pintype "bidirectional"))
    )
    (net (code "47") (name "QSPI_CS") (class "Default")
      (node (ref "R19") (pin "2") (pinfunction "2_2") (pintype "passive"))
      (node (ref "U$2") (pin "24") (pinfunction "PB11/I11/SERCOM4.3/I2SFS1_24") (pintype "bidirectional"))
      (node (ref "U2") (pin "1") (pinfunction "SSEL_1") (pintype "bidirectional"))
    )
    (net (code "48") (name "QSPI_DATA[0]") (class "Default")
      (node (ref "U$2") (pin "17") (pinfunction "PA08/I2C/AIN8/SERCOM0.0+2.1/I2SMCK_17") (pintype "bidirectional"))
      (node (ref "U2") (pin "5") (pinfunction "MOSI_5") (pintype "bidirectional"))
    )
    (net (code "49") (name "QSPI_DATA[1]") (class "Default")
      (node (ref "U$2") (pin "18") (pinfunction "PA09/I2C/I9/AIN9/SERCOM0.1+2.0/I2SFS0_18") (pintype "bidirectional"))
      (node (ref "U2") (pin "2") (pinfunction "MISO_2") (pintype "bidirectional"))
    )
    (net (code "50") (name "QSPI_DATA[2]") (class "Default")
      (node (ref "U$2") (pin "19") (pinfunction "PA10/I10/AIN10/SERCOM0+2.2/I2SCK_19") (pintype "bidirectional"))
      (node (ref "U2") (pin "3") (pinfunction "WP#/IO2_3") (pintype "bidirectional"))
    )
    (net (code "51") (name "QSPI_DATA[3]") (class "Default")
      (node (ref "U$2") (pin "20") (pinfunction "PA11/I11/AIN11/SERCOM0+2.3/I2SDO_20") (pintype "bidirectional"))
      (node (ref "U2") (pin "7") (pinfunction "HOLD#/IO3_7") (pintype "bidirectional"))
    )
    (net (code "52") (name "QSPI_SCK") (class "Default")
      (node (ref "U$2") (pin "23") (pinfunction "PB10/I10/SERCOM4.2/I2SDI_23") (pintype "bidirectional"))
      (node (ref "U2") (pin "6") (pinfunction "SCK_6") (pintype "bidirectional"))
    )
    (net (code "53") (name "RXD") (class "Default")
      (node (ref "U$2") (pin "26") (pinfunction "PB13/I13/SERCOM4.1/I2SMCK1_26") (pintype "bidirectional"))
      (node (ref "X6") (pin "35") (pinfunction "TXD0_35") (pintype "output"))
    )
    (net (code "54") (name "SCK") (class "Default")
      (node (ref "SJ3") (pin "2") (pinfunction "2_2") (pintype "passive"))
      (node (ref "U$2") (pin "30") (pinfunction "PA13/I13/I2C/SERCOM2.1+4.0_30") (pintype "bidirectional"))
      (node (ref "X1") (pin "5") (pinfunction "SCLK_5") (pintype "input"))
      (node (ref "X6") (pin "30") (pinfunction "IO18_30") (pintype "bidirectional"))
    )
    (net (code "55") (name "SCL") (class "Default")
      (node (ref "I2C") (pin "4") (pinfunction "SCL_4") (pintype "passive"))
      (node (ref "R16") (pin "2") (pinfunction "2_2") (pintype "passive"))
      (node (ref "U$2") (pin "64") (pinfunction "PB03/I3/AIN15/SERCOM5.1_64") (pintype "bidirectional"))
      (node (ref "U3") (pin "1") (pinfunction "SCL_1") (pintype "bidirectional"))
    )
    (net (code "56") (name "SDA") (class "Default")
      (node (ref "I2C") (pin "3") (pinfunction "SDA_3") (pintype "passive"))
      (node (ref "R17") (pin "2") (pinfunction "2_2") (pintype "passive"))
      (node (ref "U$2") (pin "63") (pinfunction "PB02/I2/AIN14/SERCOM5.0_63") (pintype "bidirectional"))
      (node (ref "U3") (pin "2") (pinfunction "SDA_2") (pintype "bidirectional"))
    )
    (net (code "57") (name "SD_CS") (class "Default")
      (node (ref "R18") (pin "2") (pinfunction "2_2") (pintype "passive"))
      (node (ref "U$2") (pin "59") (pinfunction "PB30/I14/SERCOM5.1/SWO_59") (pintype "bidirectional"))
      (node (ref "X1") (pin "2") (pinfunction "CS_2") (pintype "input"))
    )
    (net (code "58") (name "SPK_SD") (class "Default")
      (node (ref "IC2") (pin "4") (pinfunction "/SD_4") (pintype "input"))
      (node (ref "R22") (pin "2") (pinfunction "2_2") (pintype "passive"))
      (node (ref "U$2") (pin "51") (pinfunction "PA27/I11_51") (pintype "bidirectional"))
    )
    (net (code "59") (name "SWCLK") (class "Default")
      (node (ref "TP8") (pin "P$1") (pinfunction "P$1_P$1") (pintype "bidirectional"))
      (node (ref "U$2") (pin "57") (pinfunction "PA30/I14/SERCOM1.2/SWCLK_57") (pintype "bidirectional"))
      (node (ref "X3") (pin "4") (pinfunction "SWDCLK_4") (pintype "bidirectional"))
    )
    (net (code "60") (name "SWDIO") (class "Default")
      (node (ref "TP7") (pin "P$1") (pinfunction "P$1_P$1") (pintype "bidirectional"))
      (node (ref "U$2") (pin "58") (pinfunction "PA31/I15/SERCOM1.3/SWDIO_58") (pintype "bidirectional"))
      (node (ref "X3") (pin "2") (pinfunction "SWDIO_2") (pintype "bidirectional"))
    )
    (net (code "61") (name "TFT_BACKLITE") (class "Default")
      (node (ref "R5") (pin "1") (pinfunction "1_1") (pintype "passive"))
      (node (ref "U$2") (pin "60") (pinfunction "PB31/I15/SERCOM5.0_60") (pintype "bidirectional"))
    )
    (net (code "62") (name "TFT_CS") (class "Default")
      (node (ref "R20") (pin "2") (pinfunction "2_2") (pintype "passive"))
      (node (ref "U$2") (pin "9") (pinfunction "PB06/I6/AIN8_9") (pintype "bidirectional"))
      (node (ref "U$24") (pin "38") (pinfunction "#CS_38") (pintype "bidirectional"))
    )
    (net (code "63") (name "TFT_RD") (class "Default")
      (node (ref "U$2") (pin "5") (pinfunction "PB04/I4/AIN6_5") (pintype "bidirectional"))
      (node (ref "U$24") (pin "35") (pinfunction "#RD_35") (pintype "bidirectional"))
    )
    (net (code "64") (name "TFT_RESET") (class "Default")
      (node (ref "U$2") (pin "1") (pinfunction "PA00/EINT0/SERCOM1.0_1") (pintype "bidirectional"))
      (node (ref "U$24") (pin "10") (pinfunction "RESET_10") (pintype "bidirectional"))
    )
    (net (code "65") (name "TFT_RS") (class "Default")
      (node (ref "SJ3") (pin "1") (pinfunction "1_1") (pintype "passive"))
      (node (ref "U$2") (pin "6") (pinfunction "PB05/I5/AIN7_6") (pintype "bidirectional"))
      (node (ref "U$24") (pin "37") (pinfunction "RS_37") (pintype "bidirectional"))
    )
    (net (code "66") (name "TFT_TE") (class "Default")
      (node (ref "U$2") (pin "10") (pinfunction "PB07/I7/AIN9_10") (pintype "bidirectional"))
      (node (ref "U$24") (pin "39") (pinfunction "TE_39") (pintype "bidirectional"))
    )
    (net (code "67") (name "TFT_WR") (class "Default")
      (node (ref "U$2") (pin "12") (pinfunction "PB09/I9/AIN3/SERCOM4.1_12") (pintype "bidirectional"))
      (node (ref "U$24") (pin "36") (pinfunction "#WR_36") (pintype "bidirectional"))
    )
    (net (code "68") (name "TOUCH_XL") (class "Default")
      (node (ref "U$2") (pin "62") (pinfunction "PB01/I1/AIN13/SERCOM5.3_62") (pintype "bidirectional"))
      (node (ref "U$24") (pin "46") (pinfunction "XL_46") (pintype "bidirectional"))
    )
    (net (code "69") (name "TOUCH_XR") (class "Default")
      (node (ref "U$2") (pin "11") (pinfunction "PB08/I8/AIN2/SERCOM4.0_11") (pintype "bidirectional"))
      (node (ref "U$24") (pin "44") (pinfunction "XR_44") (pintype "bidirectional"))
    )
    (net (code "70") (name "TOUCH_YD") (class "Default")
      (node (ref "U$2") (pin "61") (pinfunction "PB00/I0/AIN12/SERCOM5.2_61") (pintype "bidirectional"))
      (node (ref "U$24") (pin "45") (pinfunction "YD_45") (pintype "bidirectional"))
    )
    (net (code "71") (name "TOUCH_YU") (class "Default")
      (node (ref "U$2") (pin "15") (pinfunction "PA06/I6/VREFC/AIN6/SERCOM0.2_15") (pintype "bidirectional"))
      (node (ref "U$24") (pin "47") (pinfunction "YU_47") (pintype "bidirectional"))
    )
    (net (code "72") (name "TXD") (class "Default")
      (node (ref "U$2") (pin "25") (pinfunction "PB12/I12/SERCOM4.0/I2SCK1_25") (pintype "bidirectional"))
      (node (ref "X6") (pin "34") (pinfunction "RXD0_34") (pintype "input"))
    )
    (net (code "73") (name "VBUS") (class "Default")
      (node (ref "PTC1") (pin "2") (pinfunction "2_2") (pintype "passive"))
      (node (ref "X4") (pin "VBUS") (pinfunction "VBUS_VBUS") (pintype "power_in"))
    )
    (net (code "74") (name "VCC") (class "Default")
      (node (ref "C7") (pin "1") (pinfunction "1_1") (pintype "passive"))
      (node (ref "I2C") (pin "2") (pinfunction "V+_2") (pintype "passive"))
      (node (ref "NEOPIX") (pin "2") (pinfunction "2_2") (pintype "passive"))
      (node (ref "SENSE") (pin "2") (pinfunction "2_2") (pintype "passive"))
      (node (ref "SJ1") (pin "2") (pinfunction "2_2") (pintype "passive"))
    )
    (net (code "75") (name "unconnected-(LED1-DO-Pad3)") (class "Default")
      (node (ref "LED1") (pin "3") (pinfunction "DO_3") (pintype "output"))
    )
    (net (code "76") (name "unconnected-(U$2C-VSW-Pad55)") (class "Default")
      (node (ref "U$2") (pin "55") (pinfunction "VSW_55") (pintype "bidirectional"))
    )
    (net (code "77") (name "unconnected-(U$24-DB8-Pad24)") (class "Default")
      (node (ref "U$24") (pin "24") (pinfunction "DB8_24") (pintype "bidirectional"))
    )
    (net (code "78") (name "unconnected-(U$24-DB9-Pad23)") (class "Default")
      (node (ref "U$24") (pin "23") (pinfunction "DB9_23") (pintype "bidirectional"))
    )
    (net (code "79") (name "unconnected-(U$24-DB10-Pad22)") (class "Default")
      (node (ref "U$24") (pin "22") (pinfunction "DB10_22") (pintype "bidirectional"))
    )
    (net (code "80") (name "unconnected-(U$24-DB11-Pad21)") (class "Default")
      (node (ref "U$24") (pin "21") (pinfunction "DB11_21") (pintype "bidirectional"))
    )
    (net (code "81") (name "unconnected-(U$24-DB12-Pad20)") (class "Default")
      (node (ref "U$24") (pin "20") (pinfunction "DB12_20") (pintype "bidirectional"))
    )
    (net (code "82") (name "unconnected-(U$24-DB13-Pad19)") (class "Default")
      (node (ref "U$24") (pin "19") (pinfunction "DB13_19") (pintype "bidirectional"))
    )
    (net (code "83") (name "unconnected-(U$24-DB14-Pad18)") (class "Default")
      (node (ref "U$24") (pin "18") (pinfunction "DB14_18") (pintype "bidirectional"))
    )
    (net (code "84") (name "unconnected-(U$24-DB15-Pad17)") (class "Default")
      (node (ref "U$24") (pin "17") (pinfunction "DB15_17") (pintype "bidirectional"))
    )
    (net (code "85") (name "unconnected-(U$24-DB16-Pad16)") (class "Default")
      (node (ref "U$24") (pin "16") (pinfunction "DB16_16") (pintype "bidirectional"))
    )
    (net (code "86") (name "unconnected-(U$24-DB17-Pad15)") (class "Default")
      (node (ref "U$24") (pin "15") (pinfunction "DB17_15") (pintype "bidirectional"))
    )
    (net (code "87") (name "unconnected-(U$24-DE-Pad14)") (class "Default")
      (node (ref "U$24") (pin "14") (pinfunction "DE_14") (pintype "bidirectional"))
    )
    (net (code "88") (name "unconnected-(U$24-DOTCLK-Pad13)") (class "Default")
      (node (ref "U$24") (pin "13") (pinfunction "DOTCLK_13") (pintype "bidirectional"))
    )
    (net (code "89") (name "unconnected-(U$24-HSYNC-Pad12)") (class "Default")
      (node (ref "U$24") (pin "12") (pinfunction "HSYNC_12") (pintype "bidirectional"))
    )
    (net (code "90") (name "unconnected-(U$24-VSYNC-Pad11)") (class "Default")
      (node (ref "U$24") (pin "11") (pinfunction "VSYNC_11") (pintype "bidirectional"))
    )
    (net (code "91") (name "unconnected-(U1-P4-Pad4)") (class "Default")
      (node (ref "U1") (pin "4") (pinfunction "P4_4") (pintype "bidirectional"))
    )
    (net (code "92") (name "unconnected-(U3-CT-Pad6)") (class "Default")
      (node (ref "U3") (pin "6") (pinfunction "CT_6") (pintype "bidirectional"))
    )
    (net (code "93") (name "unconnected-(U3-INT-Pad5)") (class "Default")
      (node (ref "U3") (pin "5") (pinfunction "INT_5") (pintype "bidirectional"))
    )
    (net (code "94") (name "unconnected-(X1-CARD_DETECT-PadCD1)") (class "Default")
      (node (ref "X1") (pin "CD1") (pinfunction "CARD_DETECT_CD1") (pintype "passive"))
    )
    (net (code "95") (name "unconnected-(X1-DAT1-Pad8)") (class "Default")
      (node (ref "X1") (pin "8") (pinfunction "DAT1_8") (pintype "bidirectional"))
    )
    (net (code "96") (name "unconnected-(X1-DAT2-Pad1)") (class "Default")
      (node (ref "X1") (pin "1") (pinfunction "DAT2_1") (pintype "bidirectional"))
    )
    (net (code "97") (name "unconnected-(X3-SWO-Pad6)") (class "Default")
      (node (ref "X3") (pin "6") (pinfunction "SWO_6") (pintype "bidirectional"))
    )
    (net (code "98") (name "unconnected-(X3-TDI-Pad8)") (class "Default")
      (node (ref "X3") (pin "8") (pinfunction "TDI_8") (pintype "bidirectional"))
    )
    (net (code "99") (name "unconnected-(X4-PadID)") (class "Default")
      (node (ref "X4") (pin "ID") (pinfunction "ID_ID") (pintype "bidirectional"))
    )
    (net (code "100") (name "unconnected-(X6-CLK-Pad20)") (class "Default")
      (node (ref "X6") (pin "20") (pinfunction "CLK_20") (pintype "bidirectional"))
    )
    (net (code "101") (name "unconnected-(X6-CMD-Pad19)") (class "Default")
      (node (ref "X6") (pin "19") (pinfunction "CMD_19") (pintype "bidirectional"))
    )
    (net (code "102") (name "unconnected-(X6-I34{slash}A1_6-Pad6)") (class "Default")
      (node (ref "X6") (pin "6") (pinfunction "I34/A1_6_6") (pintype "bidirectional"))
    )
    (net (code "103") (name "unconnected-(X6-I35{slash}A1_7-Pad7)") (class "Default")
      (node (ref "X6") (pin "7") (pinfunction "I35/A1_7_7") (pintype "bidirectional"))
    )
    (net (code "104") (name "unconnected-(X6-IO2{slash}A2_2-Pad24)") (class "Default")
      (node (ref "X6") (pin "24") (pinfunction "IO2/A2_2_24") (pintype "bidirectional"))
    )
    (net (code "105") (name "unconnected-(X6-IO4{slash}A2_0-Pad26)") (class "Default")
      (node (ref "X6") (pin "26") (pinfunction "IO4/A2_0_26") (pintype "bidirectional"))
    )
    (net (code "106") (name "unconnected-(X6-IO12{slash}A2_5-Pad14)") (class "Default")
      (node (ref "X6") (pin "14") (pinfunction "IO12/A2_5_14") (pintype "bidirectional"))
    )
    (net (code "107") (name "unconnected-(X6-IO13{slash}A2_4-Pad16)") (class "Default")
      (node (ref "X6") (pin "16") (pinfunction "IO13/A2_4_16") (pintype "bidirectional"))
    )
    (net (code "108") (name "unconnected-(X6-IO15{slash}A2_3-Pad23)") (class "Default")
      (node (ref "X6") (pin "23") (pinfunction "IO15/A2_3_23") (pintype "bidirectional"))
    )
    (net (code "109") (name "unconnected-(X6-IO16-Pad27)") (class "Default")
      (node (ref "X6") (pin "27") (pinfunction "IO16_27") (pintype "bidirectional"))
    )
    (net (code "110") (name "unconnected-(X6-IO17-Pad28)") (class "Default")
      (node (ref "X6") (pin "28") (pinfunction "IO17_28") (pintype "bidirectional"))
    )
    (net (code "111") (name "unconnected-(X6-IO21-Pad33)") (class "Default")
      (node (ref "X6") (pin "33") (pinfunction "IO21_33") (pintype "bidirectional"))
    )
    (net (code "112") (name "unconnected-(X6-IO22-Pad36)") (class "Default")
      (node (ref "X6") (pin "36") (pinfunction "IO22_36") (pintype "bidirectional"))
    )
    (net (code "113") (name "unconnected-(X6-IO25{slash}DAC1{slash}A2_8-Pad10)") (class "Default")
      (node (ref "X6") (pin "10") (pinfunction "IO25/DAC1/A2_8_10") (pintype "bidirectional"))
    )
    (net (code "114") (name "unconnected-(X6-IO26{slash}DAC2{slash}A2_9-Pad11)") (class "Default")
      (node (ref "X6") (pin "11") (pinfunction "IO26/DAC2/A2_9_11") (pintype "bidirectional"))
    )
    (net (code "115") (name "unconnected-(X6-IO27{slash}A2_7-Pad12)") (class "Default")
      (node (ref "X6") (pin "12") (pinfunction "IO27/A2_7_12") (pintype "bidirectional"))
    )
    (net (code "116") (name "unconnected-(X6-IO32{slash}A1_4{slash}X32P-Pad8)") (class "Default")
      (node (ref "X6") (pin "8") (pinfunction "IO32/A1_4/X32P_8") (pintype "bidirectional"))
    )
    (net (code "117") (name "unconnected-(X6-IO36{slash}SEN_VP{slash}A1_0-Pad4)") (class "Default")
      (node (ref "X6") (pin "4") (pinfunction "IO36/SEN_VP/A1_0_4") (pintype "passive"))
    )
    (net (code "118") (name "unconnected-(X6-IO39{slash}SEN_VN{slash}A1_3-Pad5)") (class "Default")
      (node (ref "X6") (pin "5") (pinfunction "IO39/SEN_VN/A1_3_5") (pintype "passive"))
    )
    (net (code "119") (name "unconnected-(X6-SD0-Pad21)") (class "Default")
      (node (ref "X6") (pin "21") (pinfunction "SD0_21") (pintype "bidirectional"))
    )
    (net (code "120") (name "unconnected-(X6-SD1-Pad22)") (class "Default")
      (node (ref "X6") (pin "22") (pinfunction "SD1_22") (pintype "bidirectional"))
    )
    (net (code "121") (name "unconnected-(X6-SD2-Pad17)") (class "Default")
      (node (ref "X6") (pin "17") (pinfunction "SD2_17") (pintype "bidirectional"))
    )
    (net (code "122") (name "unconnected-(X6-SD3-Pad18)") (class "Default")
      (node (ref "X6") (pin "18") (pinfunction "SD3_18") (pintype "bidirectional"))
    )
    (net (code "123") (name "~{RESET}") (class "Default")
      (node (ref "C17") (pin "2") (pinfunction "2_2") (pintype "passive"))
      (node (ref "R6") (pin "2") (pinfunction "2_2") (pintype "passive"))
      (node (ref "RESET") (pin "B") (pinfunction "S_B") (pintype "passive"))
      (node (ref "RESET") (pin "B'") (pinfunction "S1_B'") (pintype "passive"))
      (node (ref "TP9") (pin "P$1") (pinfunction "P$1_P$1") (pintype "bidirectional"))
      (node (ref "U$2") (pin "52") (pinfunction "~{RESET}_52") (pintype "bidirectional"))
      (node (ref "X3") (pin "10") (pinfunction "NRESET_10") (pintype "bidirectional"))
    )
  )
)
